# Microcontroller_Schematic.net
KiCad netlist of a schematic drawn in Altium Designer
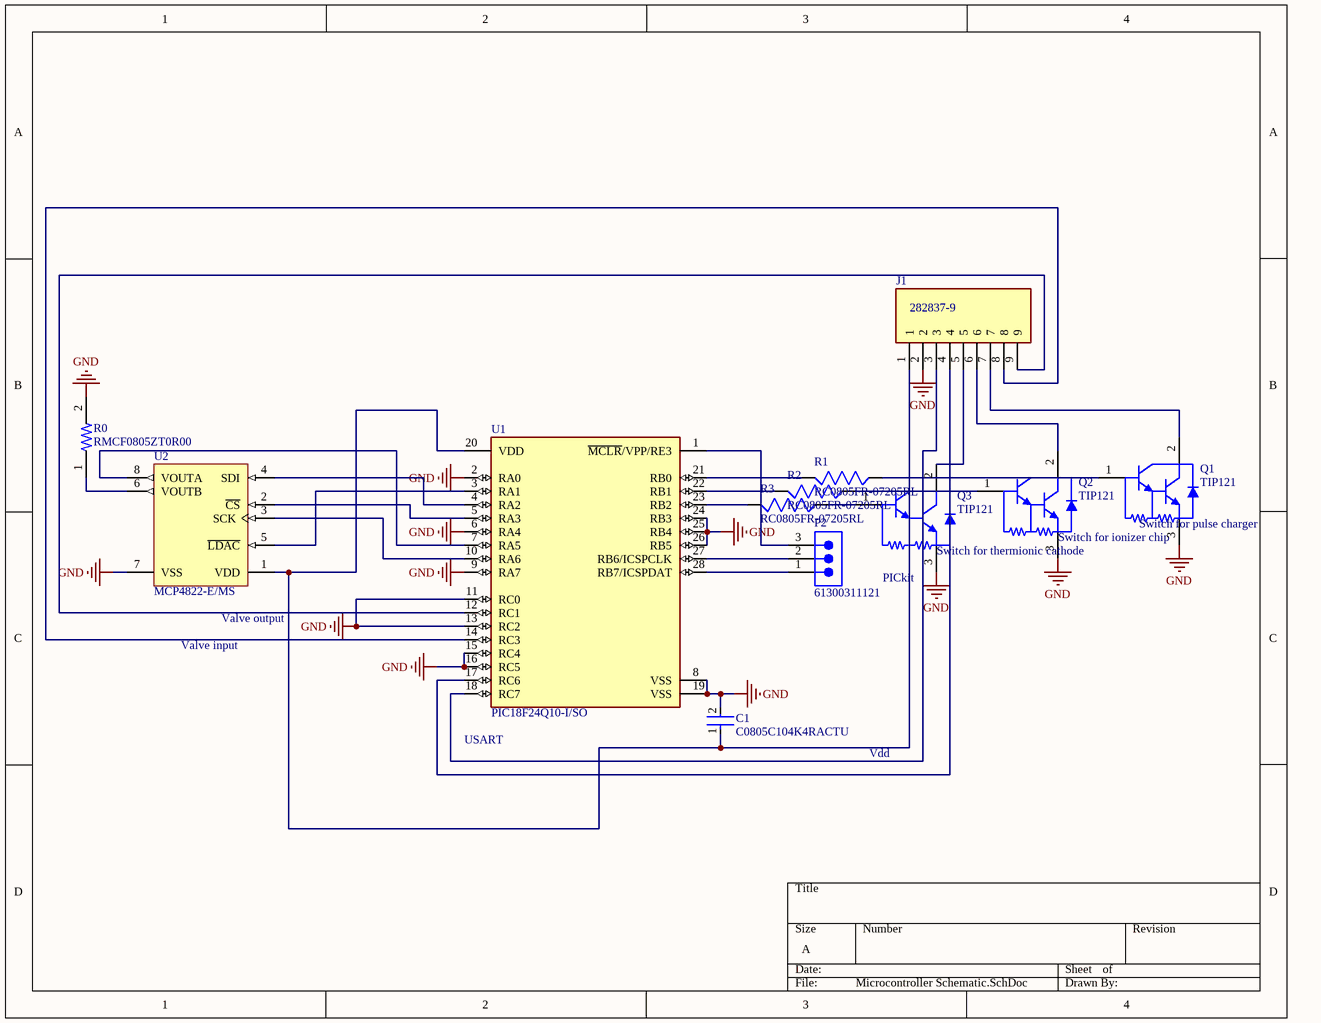
[diagram p0: Microcontroller Schematic.SchDoc]

(export (version "E")
  (design (tool "Eeschema 10.0.6"))
  (components
    (comp (ref "C1")
      (value "C0805C104K4RACTU")
      (footprint "FP-C0805C-DN-IPC_A")
      (description "CAP CER 0.1UF 16V X7R 0805")
      (fields
        (field (name "OCTOPART") "https://octopart.com/c0805c104k4ractu-kemet-92155")
        (field (name "TOLERANCE") "0.1")
      )
      (libsource (lib "C0805C104K4RAC7800") (part "CMP-2007-00274-2"))
    )
    (comp (ref "J1")
      (value "282837-9")
      (footprint "TE_282837-9:TE_282837-9")
      (fields (field (name "MF") "{'manufacturer': 'TE Connectivity'}"))
      (libsource (lib "282837-9") (part "282837-9"))
    )
    (comp (ref "P2")
      (value "61300311121")
      (footprint "61300311121")
      (libsource (lib "61300311121") (part "CMP-1502-01062-2"))
    )
    (comp (ref "Q1")
      (value "TIP121")
      (footprint "ONSC-TO-220-3-221A-09")
      (description "Plastic Medium-Power, Complementary Silicon Transistor, 3-Pin TO-220, Tube")
      (fields (field (name "MANUFACTURER") "On Semiconductor"))
      (libsource (lib "TIP121") (part "CMP-1047-00128-1"))
    )
    (comp (ref "Q2")
      (value "TIP121")
      (footprint "ONSC-TO-220-3-221A-09")
      (description "Plastic Medium-Power, Complementary Silicon Transistor, 3-Pin TO-220, Tube")
      (fields (field (name "MANUFACTURER") "On Semiconductor"))
      (libsource (lib "TIP121") (part "CMP-1047-00128-1"))
    )
    (comp (ref "Q3")
      (value "TIP121")
      (footprint "ONSC-TO-220-3-221A-09")
      (description "Plastic Medium-Power, Complementary Silicon Transistor, 3-Pin TO-220, Tube")
      (fields (field (name "MANUFACTURER") "On Semiconductor"))
      (libsource (lib "TIP121") (part "CMP-1047-00128-1"))
    )
    (comp (ref "R0")
      (value "RMCF0805ZT0R00")
      (footprint "SnapEDApcb:RESC2012X60N")
      (description "0 Ohms Jumper 0.125W, 1/8W Chip Resistor 0805 (2012 Metric) Automotive AEC-Q200 Thick Film")
      (fields (field (name "MF") "Stackpole Electronics"))
      (libsource (lib "SnapEDAsch") (part "RMCF0805ZT0R00"))
    )
    (comp (ref "R1")
      (value "RC0805FR-07205RL")
      (footprint "RESC2012X60")
      (description "RC Series 0805 0.125 W 2 kOhms 5% Â±100 ppm/Â°C SMT Thick Film Chip Resistor")
      (fields (field (name "MF") "{'manufacturer': u'YAGEO'}"))
      (libsource (lib "RC0805FR-07205RL") (part "RC0805FR-07205RL"))
    )
    (comp (ref "R2")
      (value "RC0805FR-07205RL")
      (footprint "RESC2012X60")
      (description "RC Series 0805 0.125 W 2 kOhms 5% Â±100 ppm/Â°C SMT Thick Film Chip Resistor")
      (fields (field (name "MF") "{'manufacturer': u'YAGEO'}"))
      (libsource (lib "RC0805FR-07205RL") (part "RC0805FR-07205RL"))
    )
    (comp (ref "R3")
      (value "RC0805FR-07205RL")
      (footprint "RESC2012X60")
      (description "RC Series 0805 0.125 W 2 kOhms 5% Â±100 ppm/Â°C SMT Thick Film Chip Resistor")
      (fields (field (name "MF") "{'manufacturer': u'YAGEO'}"))
      (libsource (lib "RC0805FR-07205RL") (part "RC0805FR-07205RL"))
    )
    (comp (ref "U1")
      (value "PIC18F24Q10-I/SO")
      (footprint "FP-C04-052-IPC_A")
      (description "IC MCU 8BIT 16KB FLASH 28SOIC")
      (libsource (lib "PIC18F24Q10") (part "CMP-06276-000706-1"))
    )
    (comp (ref "U2")
      (value "MCP4822-E/MS")
      (footprint "MSOP-MS8_L")
      (description "12-Bit DACs with Internal VREF and SPI Interface, 8-Pin MSOP, Extended Temperature")
      (libsource (lib "MCP4822") (part "CMP-0188-00137-2"))
    )
  )
  (nets
    (net (code "1") (name "GND") (class "Default")
      (node (ref "C1") (pin "2") (pinfunction "2_2") (pintype "passive"))
      (node (ref "J1") (pin "2") (pinfunction "2_2") (pintype "passive"))
      (node (ref "Q1") (pin "3") (pinfunction "E_3") (pintype "passive"))
      (node (ref "Q2") (pin "3") (pinfunction "E_3") (pintype "passive"))
      (node (ref "Q3") (pin "3") (pinfunction "E_3") (pintype "passive"))
      (node (ref "R0") (pin "2") (pinfunction "2_2") (pintype "passive"))
      (node (ref "U1") (pin "11") (pinfunction "RC0_11") (pintype "bidirectional"))
      (node (ref "U1") (pin "13") (pinfunction "RC2_13") (pintype "bidirectional"))
      (node (ref "U1") (pin "15") (pinfunction "RC4_15") (pintype "bidirectional"))
      (node (ref "U1") (pin "16") (pinfunction "RC5_16") (pintype "bidirectional"))
      (node (ref "U1") (pin "19") (pinfunction "VSS_19") (pintype "power_in"))
      (node (ref "U1") (pin "2") (pinfunction "RA0_2") (pintype "bidirectional"))
      (node (ref "U1") (pin "24") (pinfunction "RB3_24") (pintype "bidirectional"))
      (node (ref "U1") (pin "25") (pinfunction "RB4_25") (pintype "bidirectional"))
      (node (ref "U1") (pin "26") (pinfunction "RB5_26") (pintype "bidirectional"))
      (node (ref "U1") (pin "6") (pinfunction "RA4_6") (pintype "bidirectional"))
      (node (ref "U1") (pin "8") (pinfunction "VSS_8") (pintype "power_in"))
      (node (ref "U1") (pin "9") (pinfunction "RA7_9") (pintype "bidirectional"))
      (node (ref "U2") (pin "7") (pinfunction "VSS_7") (pintype "power_in"))
    )
    (net (code "2") (name "Net-(Q1-B)") (class "Default")
      (node (ref "Q1") (pin "1") (pinfunction "B_1") (pintype "passive"))
      (node (ref "R1") (pin "2") (pinfunction "2_2") (pintype "passive"))
    )
    (net (code "3") (name "Net-(Q1-C)") (class "Default")
      (node (ref "J1") (pin "7") (pinfunction "7_7") (pintype "passive"))
      (node (ref "Q1") (pin "2") (pinfunction "C_2") (pintype "passive"))
    )
    (net (code "4") (name "Net-(Q2-B)") (class "Default")
      (node (ref "Q2") (pin "1") (pinfunction "B_1") (pintype "passive"))
      (node (ref "R2") (pin "2") (pinfunction "2_2") (pintype "passive"))
    )
    (net (code "5") (name "Net-(Q2-C)") (class "Default")
      (node (ref "J1") (pin "6") (pinfunction "6_6") (pintype "passive"))
      (node (ref "Q2") (pin "2") (pinfunction "C_2") (pintype "passive"))
    )
    (net (code "6") (name "Net-(Q3-B)") (class "Default")
      (node (ref "Q3") (pin "1") (pinfunction "B_1") (pintype "passive"))
      (node (ref "R3") (pin "2") (pinfunction "2_2") (pintype "passive"))
    )
    (net (code "7") (name "Net-(Q3-C)") (class "Default")
      (node (ref "J1") (pin "5") (pinfunction "5_5") (pintype "passive"))
      (node (ref "Q3") (pin "2") (pinfunction "C_2") (pintype "passive"))
    )
    (net (code "8") (name "Net-(U1-RA1)") (class "Default")
      (node (ref "U1") (pin "3") (pinfunction "RA1_3") (pintype "bidirectional"))
      (node (ref "U2") (pin "5") (pinfunction "~{LDAC}_5") (pintype "input"))
    )
    (net (code "9") (name "Net-(U1-RA2)") (class "Default")
      (node (ref "U1") (pin "4") (pinfunction "RA2_4") (pintype "bidirectional"))
      (node (ref "U2") (pin "4") (pinfunction "SDI_4") (pintype "input"))
    )
    (net (code "10") (name "Net-(U1-RA3)") (class "Default")
      (node (ref "U1") (pin "5") (pinfunction "RA3_5") (pintype "bidirectional"))
      (node (ref "U2") (pin "2") (pinfunction "~{CS}_2") (pintype "input"))
    )
    (net (code "11") (name "Net-(U1-RA5)") (class "Default")
      (node (ref "U1") (pin "7") (pinfunction "RA5_7") (pintype "bidirectional"))
      (node (ref "U2") (pin "8") (pinfunction "VOUTA_8") (pintype "output"))
    )
    (net (code "12") (name "Net-(U1-RA6)") (class "Default")
      (node (ref "U1") (pin "10") (pinfunction "RA6_10") (pintype "bidirectional"))
      (node (ref "U2") (pin "3") (pinfunction "SCK_3") (pintype "input"))
    )
    (net (code "13") (name "Net-(U1-RB0)") (class "Default")
      (node (ref "R1") (pin "1") (pinfunction "1_1") (pintype "passive"))
      (node (ref "U1") (pin "21") (pinfunction "RB0_21") (pintype "bidirectional"))
    )
    (net (code "14") (name "Net-(U1-RB1)") (class "Default")
      (node (ref "R2") (pin "1") (pinfunction "1_1") (pintype "passive"))
      (node (ref "U1") (pin "22") (pinfunction "RB1_22") (pintype "bidirectional"))
    )
    (net (code "15") (name "Net-(U1-RB2)") (class "Default")
      (node (ref "R3") (pin "1") (pinfunction "1_1") (pintype "passive"))
      (node (ref "U1") (pin "23") (pinfunction "RB2_23") (pintype "bidirectional"))
    )
    (net (code "16") (name "Net-(U1-RB6{slash}ICSPCLK)") (class "Default")
      (node (ref "P2") (pin "2") (pinfunction "2_2") (pintype "passive"))
      (node (ref "U1") (pin "27") (pinfunction "RB6/ICSPCLK_27") (pintype "bidirectional"))
    )
    (net (code "17") (name "Net-(U1-RB7{slash}ICSPDAT)") (class "Default")
      (node (ref "P2") (pin "1") (pinfunction "1_1") (pintype "passive"))
      (node (ref "U1") (pin "28") (pinfunction "RB7/ICSPDAT_28") (pintype "bidirectional"))
    )
    (net (code "18") (name "Net-(U1-RC1)") (class "Default")
      (node (ref "J1") (pin "9") (pinfunction "9_9") (pintype "passive"))
      (node (ref "U1") (pin "12") (pinfunction "RC1_12") (pintype "bidirectional"))
    )
    (net (code "19") (name "Net-(U1-RC3)") (class "Default")
      (node (ref "J1") (pin "8") (pinfunction "8_8") (pintype "passive"))
      (node (ref "U1") (pin "14") (pinfunction "RC3_14") (pintype "bidirectional"))
    )
    (net (code "20") (name "Net-(U1-RC6)") (class "Default")
      (node (ref "J1") (pin "4") (pinfunction "4_4") (pintype "passive"))
      (node (ref "U1") (pin "17") (pinfunction "RC6_17") (pintype "bidirectional"))
    )
    (net (code "21") (name "Net-(U1-RC7)") (class "Default")
      (node (ref "J1") (pin "3") (pinfunction "3_3") (pintype "passive"))
      (node (ref "U1") (pin "18") (pinfunction "RC7_18") (pintype "bidirectional"))
    )
    (net (code "22") (name "Net-(U1-VDD)") (class "Default")
      (node (ref "C1") (pin "1") (pinfunction "1_1") (pintype "passive"))
      (node (ref "J1") (pin "1") (pinfunction "1_1") (pintype "passive"))
      (node (ref "U1") (pin "20") (pinfunction "VDD_20") (pintype "power_in"))
      (node (ref "U2") (pin "1") (pinfunction "VDD_1") (pintype "power_in"))
    )
    (net (code "23") (name "Net-(U1-~{MCLR}{slash}VPP{slash}RE3)") (class "Default")
      (node (ref "P2") (pin "3") (pinfunction "3_3") (pintype "passive"))
      (node (ref "U1") (pin "1") (pinfunction "~{MCLR}/VPP/RE3_1") (pintype "passive"))
    )
    (net (code "24") (name "Net-(U2-VOUTB)") (class "Default")
      (node (ref "R0") (pin "1") (pinfunction "1_1") (pintype "passive"))
      (node (ref "U2") (pin "6") (pinfunction "VOUTB_6") (pintype "output"))
    )
  )
)
